# Tecleator.net
KiCad netlist of a schematic drawn in EAGLE
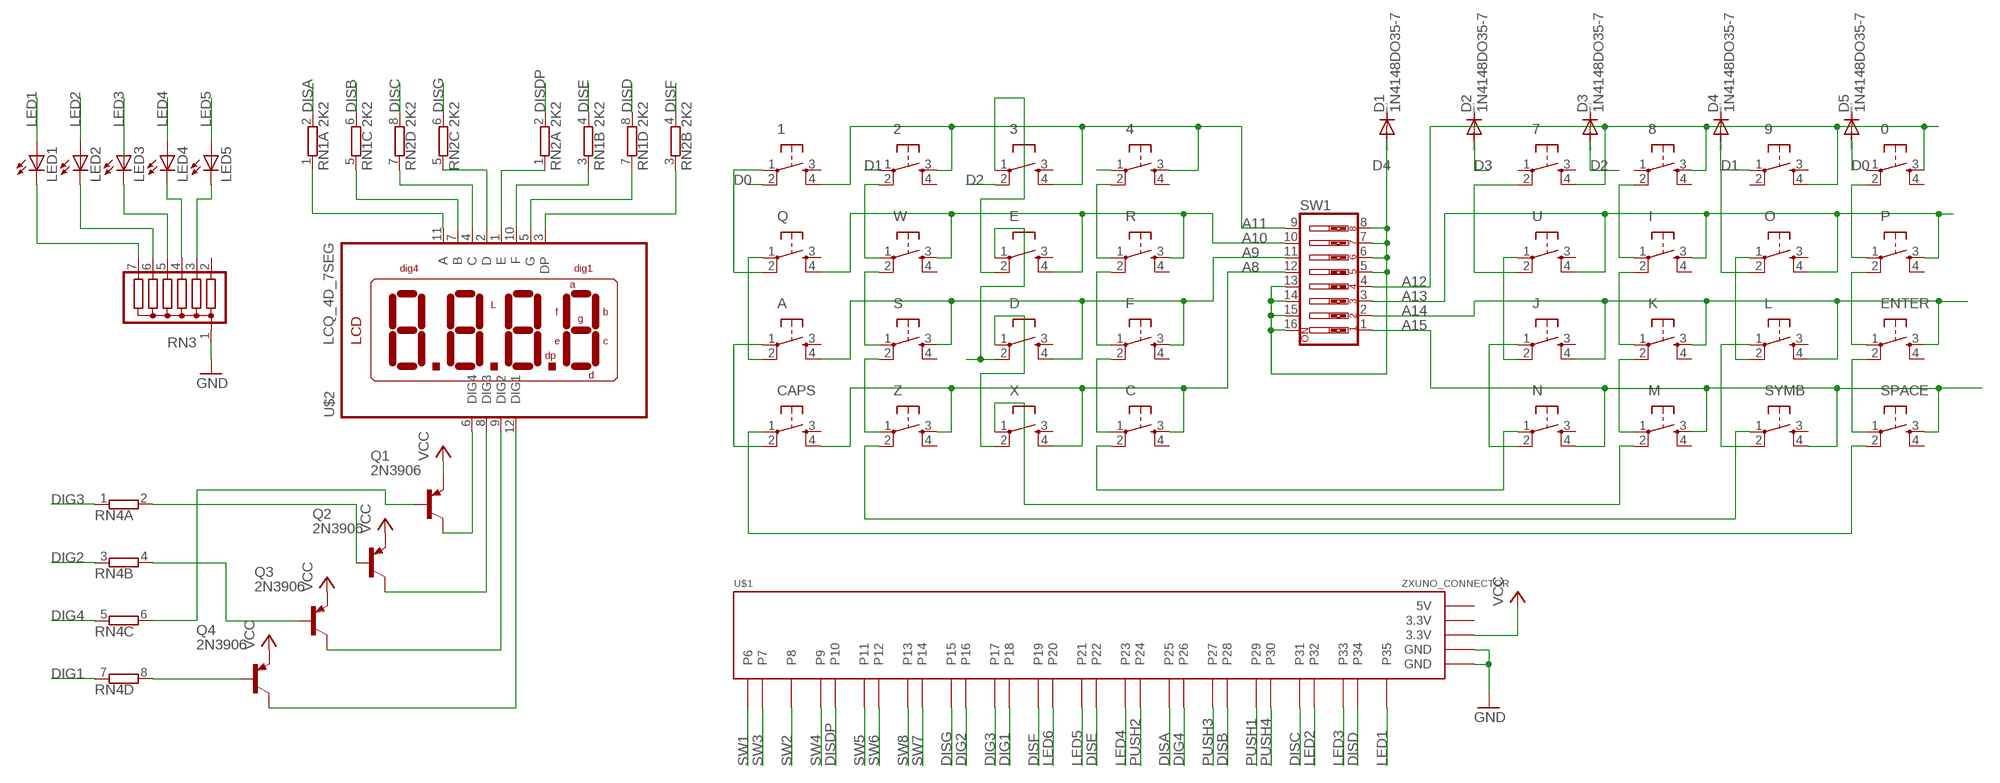
[diagram p0: schematic, sheet 1]

(export (version "E")
  (design (tool "Eeschema 10.0.6"))
  (components
    (comp (ref "0")
      (value "DTS-6")
      (footprint "eagle-import:DTS-6")
      (libsource (lib "eagle-import") (part "DTS-6"))
    )
    (comp (ref "1")
      (value "DTS-6")
      (footprint "eagle-import:DTS-6")
      (libsource (lib "eagle-import") (part "DTS-6"))
    )
    (comp (ref "2")
      (value "DTS-6")
      (footprint "eagle-import:DTS-6")
      (libsource (lib "eagle-import") (part "DTS-6"))
    )
    (comp (ref "3")
      (value "DTS-6")
      (footprint "eagle-import:DTS-6")
      (libsource (lib "eagle-import") (part "DTS-6"))
    )
    (comp (ref "4")
      (value "DTS-6")
      (footprint "eagle-import:DTS-6")
      (libsource (lib "eagle-import") (part "DTS-6"))
    )
    (comp (ref "7")
      (value "DTS-6")
      (footprint "eagle-import:DTS-6")
      (libsource (lib "eagle-import") (part "DTS-6"))
    )
    (comp (ref "8")
      (value "DTS-6")
      (footprint "eagle-import:DTS-6")
      (libsource (lib "eagle-import") (part "DTS-6"))
    )
    (comp (ref "9")
      (value "DTS-6")
      (footprint "eagle-import:DTS-6")
      (libsource (lib "eagle-import") (part "DTS-6"))
    )
    (comp (ref "A")
      (value "DTS-6")
      (footprint "eagle-import:DTS-6")
      (libsource (lib "eagle-import") (part "DTS-6"))
    )
    (comp (ref "C")
      (value "DTS-6")
      (footprint "eagle-import:DTS-6")
      (libsource (lib "eagle-import") (part "DTS-6"))
    )
    (comp (ref "CAPS")
      (value "DTS-6")
      (footprint "eagle-import:DTS-6")
      (libsource (lib "eagle-import") (part "DTS-6"))
    )
    (comp (ref "D")
      (value "DTS-6")
      (footprint "eagle-import:DTS-6")
      (libsource (lib "eagle-import") (part "DTS-6"))
    )
    (comp (ref "D1")
      (value "1N4148DO35-7")
      (footprint "eagle-import:DO35-7")
      (libsource (lib "eagle-import") (part "1N4148DO35-7"))
    )
    (comp (ref "D2")
      (value "1N4148DO35-7")
      (footprint "eagle-import:DO35-7")
      (libsource (lib "eagle-import") (part "1N4148DO35-7"))
    )
    (comp (ref "D3")
      (value "1N4148DO35-7")
      (footprint "eagle-import:DO35-7")
      (libsource (lib "eagle-import") (part "1N4148DO35-7"))
    )
    (comp (ref "D4")
      (value "1N4148DO35-7")
      (footprint "eagle-import:DO35-7")
      (libsource (lib "eagle-import") (part "1N4148DO35-7"))
    )
    (comp (ref "D5")
      (value "1N4148DO35-7")
      (footprint "eagle-import:DO35-7")
      (libsource (lib "eagle-import") (part "1N4148DO35-7"))
    )
    (comp (ref "E")
      (value "DTS-6")
      (footprint "eagle-import:DTS-6")
      (libsource (lib "eagle-import") (part "DTS-6"))
    )
    (comp (ref "ENTER")
      (value "DTS-6")
      (footprint "eagle-import:DTS-6")
      (libsource (lib "eagle-import") (part "DTS-6"))
    )
    (comp (ref "F")
      (value "DTS-6")
      (footprint "eagle-import:DTS-6")
      (libsource (lib "eagle-import") (part "DTS-6"))
    )
    (comp (ref "I")
      (value "DTS-6")
      (footprint "eagle-import:DTS-6")
      (libsource (lib "eagle-import") (part "DTS-6"))
    )
    (comp (ref "J")
      (value "DTS-6")
      (footprint "eagle-import:DTS-6")
      (libsource (lib "eagle-import") (part "DTS-6"))
    )
    (comp (ref "K")
      (value "DTS-6")
      (footprint "eagle-import:DTS-6")
      (libsource (lib "eagle-import") (part "DTS-6"))
    )
    (comp (ref "L")
      (value "DTS-6")
      (footprint "eagle-import:DTS-6")
      (libsource (lib "eagle-import") (part "DTS-6"))
    )
    (comp (ref "LED1")
      (value "LED3MM")
      (footprint "eagle-import:LED3MM")
      (libsource (lib "eagle-import") (part "LED3MM"))
    )
    (comp (ref "LED2")
      (value "LED3MM")
      (footprint "eagle-import:LED3MM")
      (libsource (lib "eagle-import") (part "LED3MM"))
    )
    (comp (ref "LED3")
      (value "LED3MM")
      (footprint "eagle-import:LED3MM")
      (libsource (lib "eagle-import") (part "LED3MM"))
    )
    (comp (ref "LED4")
      (value "LED3MM")
      (footprint "eagle-import:LED3MM")
      (libsource (lib "eagle-import") (part "LED3MM"))
    )
    (comp (ref "LED5")
      (value "LED3MM")
      (footprint "eagle-import:LED3MM")
      (libsource (lib "eagle-import") (part "LED3MM"))
    )
    (comp (ref "M")
      (value "DTS-6")
      (footprint "eagle-import:DTS-6")
      (libsource (lib "eagle-import") (part "DTS-6"))
    )
    (comp (ref "N")
      (value "DTS-6")
      (footprint "eagle-import:DTS-6")
      (libsource (lib "eagle-import") (part "DTS-6"))
    )
    (comp (ref "O")
      (value "DTS-6")
      (footprint "eagle-import:DTS-6")
      (libsource (lib "eagle-import") (part "DTS-6"))
    )
    (comp (ref "P")
      (value "DTS-6")
      (footprint "eagle-import:DTS-6")
      (libsource (lib "eagle-import") (part "DTS-6"))
    )
    (comp (ref "Q")
      (value "DTS-6")
      (footprint "eagle-import:DTS-6")
      (libsource (lib "eagle-import") (part "DTS-6"))
    )
    (comp (ref "Q1")
      (value "2N3906")
      (footprint "eagle-import:TO92")
      (libsource (lib "eagle-import") (part "2N3906"))
    )
    (comp (ref "Q2")
      (value "2N3906")
      (footprint "eagle-import:TO92")
      (libsource (lib "eagle-import") (part "2N3906"))
    )
    (comp (ref "Q3")
      (value "2N3906")
      (footprint "eagle-import:TO92")
      (libsource (lib "eagle-import") (part "2N3906"))
    )
    (comp (ref "Q4")
      (value "2N3906")
      (footprint "eagle-import:TO92")
      (libsource (lib "eagle-import") (part "2N3906"))
    )
    (comp (ref "R")
      (value "DTS-6")
      (footprint "eagle-import:DTS-6")
      (libsource (lib "eagle-import") (part "DTS-6"))
    )
    (comp (ref "RN1")
      (value "2K2")
      (footprint "eagle-import:SIL8")
      (libsource (lib "eagle-import") (part "E4R"))
    )
    (comp (ref "RN2")
      (value "2K2")
      (footprint "eagle-import:SIL8")
      (libsource (lib "eagle-import") (part "E4R"))
    )
    (comp (ref "RN3")
      (value "G06R")
      (footprint "eagle-import:SIL7")
      (libsource (lib "eagle-import") (part "G06R"))
    )
    (comp (ref "RN4")
      (value "E4R")
      (footprint "eagle-import:SIL8")
      (libsource (lib "eagle-import") (part "E4R"))
    )
    (comp (ref "S")
      (value "DTS-6")
      (footprint "eagle-import:DTS-6")
      (libsource (lib "eagle-import") (part "DTS-6"))
    )
    (comp (ref "SPACE")
      (value "DTS-6")
      (footprint "eagle-import:DTS-6")
      (libsource (lib "eagle-import") (part "DTS-6"))
    )
    (comp (ref "SW1")
      (value "SW_DIP-8")
      (footprint "eagle-import:EDG-08")
      (libsource (lib "eagle-import") (part "SW_DIP-8"))
    )
    (comp (ref "SYMB")
      (value "DTS-6")
      (footprint "eagle-import:DTS-6")
      (libsource (lib "eagle-import") (part "DTS-6"))
    )
    (comp (ref "U")
      (value "DTS-6")
      (footprint "eagle-import:DTS-6")
      (libsource (lib "eagle-import") (part "DTS-6"))
    )
    (comp (ref "U$1")
      (value "ZXUNO_CONNECTOR")
      (footprint "eagle-import:ZXUNO_CONNECTOR")
      (libsource (lib "eagle-import") (part "ZXUNO_CONNECTOR"))
    )
    (comp (ref "U$2")
      (value "LCQ_4D_7SEG")
      (footprint "eagle-import:LDQ_4D_7SEG")
      (libsource (lib "eagle-import") (part "LCQ_4D_7SEG"))
    )
    (comp (ref "W")
      (value "DTS-6")
      (footprint "eagle-import:DTS-6")
      (libsource (lib "eagle-import") (part "DTS-6"))
    )
    (comp (ref "X")
      (value "DTS-6")
      (footprint "eagle-import:DTS-6")
      (libsource (lib "eagle-import") (part "DTS-6"))
    )
    (comp (ref "Z")
      (value "DTS-6")
      (footprint "eagle-import:DTS-6")
      (libsource (lib "eagle-import") (part "DTS-6"))
    )
  )
  (nets
    (net (code "1") (name "/3.3V") (class "Default")
      (node (ref "U$1") (pin "3.3V@1") (pinfunction "3.3V_3.3V@1") (pintype "power_in"))
    )
    (net (code "2") (name "/5V") (class "Default")
      (node (ref "U$1") (pin "5V") (pinfunction "5V_5V") (pintype "power_in"))
    )
    (net (code "3") (name "/A8") (class "Default")
      (node (ref "C") (pin "3") (pinfunction "3_3") (pintype "passive"))
      (node (ref "CAPS") (pin "4") (pinfunction "4_4") (pintype "passive"))
      (node (ref "SW1") (pin "12") (pinfunction "12_12") (pintype "passive"))
      (node (ref "X") (pin "4") (pinfunction "4_4") (pintype "passive"))
      (node (ref "Z") (pin "3") (pinfunction "3_3") (pintype "passive"))
    )
    (net (code "4") (name "/A9") (class "Default")
      (node (ref "A") (pin "4") (pinfunction "4_4") (pintype "passive"))
      (node (ref "D") (pin "4") (pinfunction "4_4") (pintype "passive"))
      (node (ref "F") (pin "3") (pinfunction "3_3") (pintype "passive"))
      (node (ref "S") (pin "3") (pinfunction "3_3") (pintype "passive"))
      (node (ref "SW1") (pin "11") (pinfunction "11_11") (pintype "passive"))
    )
    (net (code "5") (name "/A10") (class "Default")
      (node (ref "E") (pin "4") (pinfunction "4_4") (pintype "passive"))
      (node (ref "Q") (pin "4") (pinfunction "4_4") (pintype "passive"))
      (node (ref "R") (pin "3") (pinfunction "3_3") (pintype "passive"))
      (node (ref "SW1") (pin "10") (pinfunction "10_10") (pintype "passive"))
      (node (ref "W") (pin "3") (pinfunction "3_3") (pintype "passive"))
    )
    (net (code "6") (name "/A11") (class "Default")
      (node (ref "1") (pin "4") (pinfunction "4_4") (pintype "passive"))
      (node (ref "2") (pin "3") (pinfunction "3_3") (pintype "passive"))
      (node (ref "3") (pin "4") (pinfunction "4_4") (pintype "passive"))
      (node (ref "4") (pin "3") (pinfunction "3_3") (pintype "passive"))
      (node (ref "SW1") (pin "9") (pinfunction "9_9") (pintype "passive"))
    )
    (net (code "7") (name "/A12") (class "Default")
      (node (ref "0") (pin "3") (pinfunction "3_3") (pintype "passive"))
      (node (ref "7") (pin "4") (pinfunction "4_4") (pintype "passive"))
      (node (ref "8") (pin "3") (pinfunction "3_3") (pintype "passive"))
      (node (ref "9") (pin "4") (pinfunction "4_4") (pintype "passive"))
      (node (ref "SW1") (pin "4") (pinfunction "4_4") (pintype "passive"))
    )
    (net (code "8") (name "/A13") (class "Default")
      (node (ref "I") (pin "3") (pinfunction "3_3") (pintype "passive"))
      (node (ref "O") (pin "4") (pinfunction "4_4") (pintype "passive"))
      (node (ref "P") (pin "3") (pinfunction "3_3") (pintype "passive"))
      (node (ref "SW1") (pin "3") (pinfunction "3_3") (pintype "passive"))
      (node (ref "U") (pin "4") (pinfunction "4_4") (pintype "passive"))
    )
    (net (code "9") (name "/A14") (class "Default")
      (node (ref "ENTER") (pin "3") (pinfunction "3_3") (pintype "passive"))
      (node (ref "J") (pin "4") (pinfunction "4_4") (pintype "passive"))
      (node (ref "K") (pin "3") (pinfunction "3_3") (pintype "passive"))
      (node (ref "L") (pin "4") (pinfunction "4_4") (pintype "passive"))
      (node (ref "SW1") (pin "2") (pinfunction "2_2") (pintype "passive"))
    )
    (net (code "10") (name "/A15") (class "Default")
      (node (ref "M") (pin "3") (pinfunction "3_3") (pintype "passive"))
      (node (ref "N") (pin "4") (pinfunction "4_4") (pintype "passive"))
      (node (ref "SPACE") (pin "3") (pinfunction "3_3") (pintype "passive"))
      (node (ref "SW1") (pin "1") (pinfunction "1_1") (pintype "passive"))
      (node (ref "SYMB") (pin "4") (pinfunction "4_4") (pintype "passive"))
    )
    (net (code "11") (name "/D0") (class "Default")
      (node (ref "1") (pin "2") (pinfunction "2_2") (pintype "passive"))
      (node (ref "D5") (pin "A") (pinfunction "A_A") (pintype "passive"))
    )
    (net (code "12") (name "/D1") (class "Default")
      (node (ref "2") (pin "1") (pinfunction "1_1") (pintype "passive"))
      (node (ref "9") (pin "1") (pinfunction "1_1") (pintype "passive"))
      (node (ref "D4") (pin "A") (pinfunction "A_A") (pintype "passive"))
      (node (ref "O") (pin "2") (pinfunction "2_2") (pintype "passive"))
    )
    (net (code "13") (name "/D2") (class "Default")
      (node (ref "3") (pin "2") (pinfunction "2_2") (pintype "passive"))
      (node (ref "D3") (pin "A") (pinfunction "A_A") (pintype "passive"))
    )
    (net (code "14") (name "/D3") (class "Default")
      (node (ref "4") (pin "1") (pinfunction "1_1") (pintype "passive"))
      (node (ref "D2") (pin "A") (pinfunction "A_A") (pintype "passive"))
    )
    (net (code "15") (name "/D4") (class "Default")
      (node (ref "D1") (pin "A") (pinfunction "A_A") (pintype "passive"))
      (node (ref "SW1") (pin "13") (pinfunction "13_13") (pintype "passive"))
      (node (ref "SW1") (pin "14") (pinfunction "14_14") (pintype "passive"))
      (node (ref "SW1") (pin "15") (pinfunction "15_15") (pintype "passive"))
      (node (ref "SW1") (pin "16") (pinfunction "16_16") (pintype "passive"))
      (node (ref "SW1") (pin "5") (pinfunction "5_5") (pintype "passive"))
      (node (ref "SW1") (pin "6") (pinfunction "6_6") (pintype "passive"))
      (node (ref "SW1") (pin "7") (pinfunction "7_7") (pintype "passive"))
      (node (ref "SW1") (pin "8") (pinfunction "8_8") (pintype "passive"))
    )
    (net (code "16") (name "/DIG1") (class "Default")
      (node (ref "RN4") (pin "7") (pinfunction "1_7") (pintype "passive"))
      (node (ref "U$1") (pin "P18") (pinfunction "P18_P18") (pintype "bidirectional"))
    )
    (net (code "17") (name "/DIG2") (class "Default")
      (node (ref "RN4") (pin "3") (pinfunction "1_3") (pintype "passive"))
      (node (ref "U$1") (pin "P16") (pinfunction "P16_P16") (pintype "bidirectional"))
    )
    (net (code "18") (name "/DIG3") (class "Default")
      (node (ref "RN4") (pin "1") (pinfunction "1_1") (pintype "passive"))
      (node (ref "U$1") (pin "P17") (pinfunction "P17_P17") (pintype "bidirectional"))
    )
    (net (code "19") (name "/DIG4") (class "Default")
      (node (ref "RN4") (pin "5") (pinfunction "1_5") (pintype "passive"))
      (node (ref "U$1") (pin "P26") (pinfunction "P26_P26") (pintype "bidirectional"))
    )
    (net (code "20") (name "/DISA") (class "Default")
      (node (ref "RN1") (pin "2") (pinfunction "2_2") (pintype "passive"))
      (node (ref "U$1") (pin "P25") (pinfunction "P25_P25") (pintype "bidirectional"))
    )
    (net (code "21") (name "/DISB") (class "Default")
      (node (ref "RN1") (pin "6") (pinfunction "2_6") (pintype "passive"))
      (node (ref "U$1") (pin "P28") (pinfunction "P28_P28") (pintype "bidirectional"))
    )
    (net (code "22") (name "/DISC") (class "Default")
      (node (ref "RN2") (pin "8") (pinfunction "2_8") (pintype "passive"))
      (node (ref "U$1") (pin "P31") (pinfunction "P31_P31") (pintype "bidirectional"))
    )
    (net (code "23") (name "/DISD") (class "Default")
      (node (ref "RN1") (pin "8") (pinfunction "2_8") (pintype "passive"))
      (node (ref "U$1") (pin "P34") (pinfunction "P34_P34") (pintype "bidirectional"))
    )
    (net (code "24") (name "/DISDP") (class "Default")
      (node (ref "RN2") (pin "2") (pinfunction "2_2") (pintype "passive"))
      (node (ref "U$1") (pin "P10") (pinfunction "P10_P10") (pintype "bidirectional"))
    )
    (net (code "25") (name "/DISE") (class "Default")
      (node (ref "RN1") (pin "4") (pinfunction "2_4") (pintype "passive"))
      (node (ref "U$1") (pin "P22") (pinfunction "P22_P22") (pintype "bidirectional"))
    )
    (net (code "26") (name "/DISF") (class "Default")
      (node (ref "RN2") (pin "4") (pinfunction "2_4") (pintype "passive"))
      (node (ref "U$1") (pin "P19") (pinfunction "P19_P19") (pintype "bidirectional"))
    )
    (net (code "27") (name "/DISG") (class "Default")
      (node (ref "RN2") (pin "6") (pinfunction "2_6") (pintype "passive"))
      (node (ref "U$1") (pin "P15") (pinfunction "P15_P15") (pintype "bidirectional"))
    )
    (net (code "28") (name "/LED1") (class "Default")
      (node (ref "LED1") (pin "A") (pinfunction "A_A") (pintype "passive"))
      (node (ref "U$1") (pin "P35") (pinfunction "P35_P35") (pintype "bidirectional"))
    )
    (net (code "29") (name "/LED2") (class "Default")
      (node (ref "LED2") (pin "A") (pinfunction "A_A") (pintype "passive"))
      (node (ref "U$1") (pin "P32") (pinfunction "P32_P32") (pintype "bidirectional"))
    )
    (net (code "30") (name "/LED3") (class "Default")
      (node (ref "LED3") (pin "A") (pinfunction "A_A") (pintype "passive"))
      (node (ref "U$1") (pin "P33") (pinfunction "P33_P33") (pintype "bidirectional"))
    )
    (net (code "31") (name "/LED4") (class "Default")
      (node (ref "LED4") (pin "A") (pinfunction "A_A") (pintype "passive"))
      (node (ref "U$1") (pin "P23") (pinfunction "P23_P23") (pintype "bidirectional"))
    )
    (net (code "32") (name "/LED5") (class "Default")
      (node (ref "LED5") (pin "A") (pinfunction "A_A") (pintype "passive"))
      (node (ref "U$1") (pin "P21") (pinfunction "P21_P21") (pintype "bidirectional"))
    )
    (net (code "33") (name "/LED6") (class "Default")
      (node (ref "U$1") (pin "P20") (pinfunction "P20_P20") (pintype "bidirectional"))
    )
    (net (code "34") (name "/PUSH1") (class "Default")
      (node (ref "U$1") (pin "P29") (pinfunction "P29_P29") (pintype "bidirectional"))
    )
    (net (code "35") (name "/PUSH2") (class "Default")
      (node (ref "U$1") (pin "P24") (pinfunction "P24_P24") (pintype "bidirectional"))
    )
    (net (code "36") (name "/PUSH3") (class "Default")
      (node (ref "U$1") (pin "P27") (pinfunction "P27_P27") (pintype "bidirectional"))
    )
    (net (code "37") (name "/PUSH4") (class "Default")
      (node (ref "U$1") (pin "P30") (pinfunction "P30_P30") (pintype "bidirectional"))
    )
    (net (code "38") (name "/SW1") (class "Default")
      (node (ref "U$1") (pin "P6") (pinfunction "P6_P6") (pintype "bidirectional"))
    )
    (net (code "39") (name "/SW2") (class "Default")
      (node (ref "U$1") (pin "P8") (pinfunction "P8_P8") (pintype "bidirectional"))
    )
    (net (code "40") (name "/SW3") (class "Default")
      (node (ref "U$1") (pin "P7") (pinfunction "P7_P7") (pintype "bidirectional"))
    )
    (net (code "41") (name "/SW4") (class "Default")
      (node (ref "U$1") (pin "P9") (pinfunction "P9_P9") (pintype "bidirectional"))
    )
    (net (code "42") (name "/SW5") (class "Default")
      (node (ref "U$1") (pin "P11") (pinfunction "P11_P11") (pintype "bidirectional"))
    )
    (net (code "43") (name "/SW6") (class "Default")
      (node (ref "U$1") (pin "P12") (pinfunction "P12_P12") (pintype "bidirectional"))
    )
    (net (code "44") (name "/SW7") (class "Default")
      (node (ref "U$1") (pin "P14") (pinfunction "P14_P14") (pintype "bidirectional"))
    )
    (net (code "45") (name "/SW8") (class "Default")
      (node (ref "U$1") (pin "P13") (pinfunction "P13_P13") (pintype "bidirectional"))
    )
    (net (code "46") (name "GND") (class "Default")
      (node (ref "RN3") (pin "1") (pinfunction "1_1") (pintype "passive"))
      (node (ref "U$1") (pin "GND@1") (pinfunction "GND_GND@1") (pintype "power_in"))
      (node (ref "U$1") (pin "GND@2") (pinfunction "GND_GND@2") (pintype "power_in"))
    )
    (net (code "47") (name "Net-(0-Pad2)") (class "Default")
      (node (ref "0") (pin "2") (pinfunction "2_2") (pintype "passive"))
      (node (ref "P") (pin "1") (pinfunction "1_1") (pintype "passive"))
    )
    (net (code "48") (name "Net-(1-Pad1)") (class "Default")
      (node (ref "1") (pin "1") (pinfunction "1_1") (pintype "passive"))
      (node (ref "Q") (pin "2") (pinfunction "2_2") (pintype "passive"))
    )
    (net (code "49") (name "Net-(2-Pad2)") (class "Default")
      (node (ref "2") (pin "2") (pinfunction "2_2") (pintype "passive"))
      (node (ref "W") (pin "1") (pinfunction "1_1") (pintype "passive"))
    )
    (net (code "50") (name "Net-(3-Pad1)") (class "Default")
      (node (ref "3") (pin "1") (pinfunction "1_1") (pintype "passive"))
      (node (ref "E") (pin "2") (pinfunction "2_2") (pintype "passive"))
    )
    (net (code "51") (name "Net-(4-Pad2)") (class "Default")
      (node (ref "4") (pin "2") (pinfunction "2_2") (pintype "passive"))
      (node (ref "R") (pin "1") (pinfunction "1_1") (pintype "passive"))
    )
    (net (code "52") (name "Net-(7-Pad2)") (class "Default")
      (node (ref "7") (pin "2") (pinfunction "2_2") (pintype "passive"))
      (node (ref "U") (pin "2") (pinfunction "2_2") (pintype "passive"))
    )
    (net (code "53") (name "Net-(8-Pad2)") (class "Default")
      (node (ref "8") (pin "2") (pinfunction "2_2") (pintype "passive"))
      (node (ref "I") (pin "1") (pinfunction "1_1") (pintype "passive"))
    )
    (net (code "54") (name "Net-(A-Pad1)") (class "Default")
      (node (ref "A") (pin "1") (pinfunction "1_1") (pintype "passive"))
      (node (ref "CAPS") (pin "2") (pinfunction "2_2") (pintype "passive"))
    )
    (net (code "55") (name "Net-(A-Pad2)") (class "Default")
      (node (ref "A") (pin "2") (pinfunction "2_2") (pintype "passive"))
      (node (ref "Q") (pin "1") (pinfunction "1_1") (pintype "passive"))
    )
    (net (code "56") (name "Net-(C-Pad1)") (class "Default")
      (node (ref "C") (pin "1") (pinfunction "1_1") (pintype "passive"))
      (node (ref "F") (pin "2") (pinfunction "2_2") (pintype "passive"))
    )
    (net (code "57") (name "Net-(C-Pad2)") (class "Default")
      (node (ref "C") (pin "2") (pinfunction "2_2") (pintype "passive"))
      (node (ref "N") (pin "1") (pinfunction "1_1") (pintype "passive"))
    )
    (net (code "58") (name "Net-(CAPS-Pad1)") (class "Default")
      (node (ref "CAPS") (pin "1") (pinfunction "1_1") (pintype "passive"))
      (node (ref "SPACE") (pin "2") (pinfunction "2_2") (pintype "passive"))
    )
    (net (code "59") (name "Net-(D-Pad1)") (class "Default")
      (node (ref "D") (pin "1") (pinfunction "1_1") (pintype "passive"))
      (node (ref "X") (pin "2") (pinfunction "2_2") (pintype "passive"))
    )
    (net (code "60") (name "Net-(D-Pad2)") (class "Default")
      (node (ref "D") (pin "2") (pinfunction "2_2") (pintype "passive"))
      (node (ref "E") (pin "1") (pinfunction "1_1") (pintype "passive"))
    )
    (net (code "61") (name "Net-(ENTER-Pad1)") (class "Default")
      (node (ref "ENTER") (pin "1") (pinfunction "1_1") (pintype "passive"))
      (node (ref "P") (pin "2") (pinfunction "2_2") (pintype "passive"))
    )
    (net (code "62") (name "Net-(ENTER-Pad2)") (class "Default")
      (node (ref "ENTER") (pin "2") (pinfunction "2_2") (pintype "passive"))
      (node (ref "SPACE") (pin "1") (pinfunction "1_1") (pintype "passive"))
    )
    (net (code "63") (name "Net-(F-Pad1)") (class "Default")
      (node (ref "F") (pin "1") (pinfunction "1_1") (pintype "passive"))
      (node (ref "R") (pin "2") (pinfunction "2_2") (pintype "passive"))
    )
    (net (code "64") (name "Net-(I-Pad2)") (class "Default")
      (node (ref "I") (pin "2") (pinfunction "2_2") (pintype "passive"))
      (node (ref "K") (pin "1") (pinfunction "1_1") (pintype "passive"))
    )
    (net (code "65") (name "Net-(J-Pad1)") (class "Default")
      (node (ref "J") (pin "1") (pinfunction "1_1") (pintype "passive"))
      (node (ref "N") (pin "2") (pinfunction "2_2") (pintype "passive"))
    )
    (net (code "66") (name "Net-(J-Pad2)") (class "Default")
      (node (ref "J") (pin "2") (pinfunction "2_2") (pintype "passive"))
      (node (ref "U") (pin "1") (pinfunction "1_1") (pintype "passive"))
    )
    (net (code "67") (name "Net-(K-Pad2)") (class "Default")
      (node (ref "K") (pin "2") (pinfunction "2_2") (pintype "passive"))
      (node (ref "M") (pin "1") (pinfunction "1_1") (pintype "passive"))
    )
    (net (code "68") (name "Net-(L-Pad1)") (class "Default")
      (node (ref "L") (pin "1") (pinfunction "1_1") (pintype "passive"))
      (node (ref "SYMB") (pin "2") (pinfunction "2_2") (pintype "passive"))
    )
    (net (code "69") (name "Net-(L-Pad2)") (class "Default")
      (node (ref "L") (pin "2") (pinfunction "2_2") (pintype "passive"))
      (node (ref "O") (pin "1") (pinfunction "1_1") (pintype "passive"))
    )
    (net (code "70") (name "Net-(LED1-C)") (class "Default")
      (node (ref "LED1") (pin "K") (pinfunction "C_K") (pintype "passive"))
      (node (ref "RN3") (pin "7") (pinfunction "7_7") (pintype "passive"))
    )
    (net (code "71") (name "Net-(LED2-C)") (class "Default")
      (node (ref "LED2") (pin "K") (pinfunction "C_K") (pintype "passive"))
      (node (ref "RN3") (pin "6") (pinfunction "6_6") (pintype "passive"))
    )
    (net (code "72") (name "Net-(LED3-C)") (class "Default")
      (node (ref "LED3") (pin "K") (pinfunction "C_K") (pintype "passive"))
      (node (ref "RN3") (pin "5") (pinfunction "5_5") (pintype "passive"))
    )
    (net (code "73") (name "Net-(LED4-C)") (class "Default")
      (node (ref "LED4") (pin "K") (pinfunction "C_K") (pintype "passive"))
      (node (ref "RN3") (pin "4") (pinfunction "4_4") (pintype "passive"))
    )
    (net (code "74") (name "Net-(LED5-C)") (class "Default")
      (node (ref "LED5") (pin "K") (pinfunction "C_K") (pintype "passive"))
      (node (ref "RN3") (pin "3") (pinfunction "3_3") (pintype "passive"))
    )
    (net (code "75") (name "Net-(M-Pad2)") (class "Default")
      (node (ref "M") (pin "2") (pinfunction "2_2") (pintype "passive"))
      (node (ref "X") (pin "1") (pinfunction "1_1") (pintype "passive"))
    )
    (net (code "76") (name "Net-(Q1-B)") (class "Default")
      (node (ref "Q1") (pin "2") (pinfunction "B_2") (pintype "passive"))
      (node (ref "RN4") (pin "6") (pinfunction "2_6") (pintype "passive"))
    )
    (net (code "77") (name "Net-(Q1-C)") (class "Default")
      (node (ref "Q1") (pin "1") (pinfunction "C_1") (pintype "passive"))
      (node (ref "U$2") (pin "6") (pinfunction "DIG4_6") (pintype "input"))
    )
    (net (code "78") (name "Net-(Q2-B)") (class "Default")
      (node (ref "Q2") (pin "2") (pinfunction "B_2") (pintype "passive"))
      (node (ref "RN4") (pin "2") (pinfunction "2_2") (pintype "passive"))
    )
    (net (code "79") (name "Net-(Q2-C)") (class "Default")
      (node (ref "Q2") (pin "1") (pinfunction "C_1") (pintype "passive"))
      (node (ref "U$2") (pin "8") (pinfunction "DIG3_8") (pintype "input"))
    )
    (net (code "80") (name "Net-(Q3-B)") (class "Default")
      (node (ref "Q3") (pin "2") (pinfunction "B_2") (pintype "passive"))
      (node (ref "RN4") (pin "4") (pinfunction "2_4") (pintype "passive"))
    )
    (net (code "81") (name "Net-(Q3-C)") (class "Default")
      (node (ref "Q3") (pin "1") (pinfunction "C_1") (pintype "passive"))
      (node (ref "U$2") (pin "9") (pinfunction "DIG2_9") (pintype "input"))
    )
    (net (code "82") (name "Net-(Q4-B)") (class "Default")
      (node (ref "Q4") (pin "2") (pinfunction "B_2") (pintype "passive"))
      (node (ref "RN4") (pin "8") (pinfunction "2_8") (pintype "passive"))
    )
    (net (code "83") (name "Net-(Q4-C)") (class "Default")
      (node (ref "Q4") (pin "1") (pinfunction "C_1") (pintype "passive"))
      (node (ref "U$2") (pin "12") (pinfunction "DIG1_12") (pintype "input"))
    )
    (net (code "84") (name "Net-(RN1B-1)") (class "Default")
      (node (ref "RN1") (pin "3") (pinfunction "1_3") (pintype "passive"))
      (node (ref "U$2") (pin "10") (pinfunction "F_10") (pintype "input"))
    )
    (net (code "85") (name "Net-(RN1C-1)") (class "Default")
      (node (ref "RN1") (pin "5") (pinfunction "1_5") (pintype "passive"))
      (node (ref "U$2") (pin "7") (pinfunction "B_7") (pintype "input"))
    )
    (net (code "86") (name "Net-(RN1D-1)") (class "Default")
      (node (ref "RN1") (pin "7") (pinfunction "1_7") (pintype "passive"))
      (node (ref "U$2") (pin "5") (pinfunction "G_5") (pintype "input"))
    )
    (net (code "87") (name "Net-(RN2B-1)") (class "Default")
      (node (ref "RN2") (pin "3") (pinfunction "1_3") (pintype "passive"))
      (node (ref "U$2") (pin "3") (pinfunction "DP_3") (pintype "input"))
    )
    (net (code "88") (name "Net-(RN2C-1)") (class "Default")
      (node (ref "RN2") (pin "5") (pinfunction "1_5") (pintype "passive"))
      (node (ref "U$2") (pin "2") (pinfunction "D_2") (pintype "input"))
    )
    (net (code "89") (name "Net-(RN2D-1)") (class "Default")
      (node (ref "RN2") (pin "7") (pinfunction "1_7") (pintype "passive"))
      (node (ref "U$2") (pin "4") (pinfunction "C_4") (pintype "input"))
    )
    (net (code "90") (name "Net-(S-Pad1)") (class "Default")
      (node (ref "S") (pin "1") (pinfunction "1_1") (pintype "passive"))
      (node (ref "W") (pin "2") (pinfunction "2_2") (pintype "passive"))
    )
    (net (code "91") (name "Net-(S-Pad2)") (class "Default")
      (node (ref "S") (pin "2") (pinfunction "2_2") (pintype "passive"))
      (node (ref "Z") (pin "1") (pinfunction "1_1") (pintype "passive"))
    )
    (net (code "92") (name "Net-(SYMB-Pad1)") (class "Default")
      (node (ref "SYMB") (pin "1") (pinfunction "1_1") (pintype "passive"))
      (node (ref "Z") (pin "2") (pinfunction "2_2") (pintype "passive"))
    )
    (net (code "93") (name "Net-(U$2-A)") (class "Default")
      (node (ref "RN1") (pin "1") (pinfunction "1_1") (pintype "passive"))
      (node (ref "U$2") (pin "11") (pinfunction "A_11") (pintype "input"))
    )
    (net (code "94") (name "Net-(U$2-E)") (class "Default")
      (node (ref "RN2") (pin "1") (pinfunction "1_1") (pintype "passive"))
      (node (ref "U$2") (pin "1") (pinfunction "E_1") (pintype "input"))
    )
    (net (code "95") (name "VCC") (class "Default")
      (node (ref "Q1") (pin "3") (pinfunction "E_3") (pintype "passive"))
      (node (ref "Q2") (pin "3") (pinfunction "E_3") (pintype "passive"))
      (node (ref "Q3") (pin "3") (pinfunction "E_3") (pintype "passive"))
      (node (ref "Q4") (pin "3") (pinfunction "E_3") (pintype "passive"))
      (node (ref "U$1") (pin "3.3V@2") (pinfunction "3.3V_3.3V@2") (pintype "power_in"))
    )
    (net (code "96") (name "unconnected-(0-Pad1)") (class "Default")
      (node (ref "0") (pin "1") (pinfunction "1_1") (pintype "passive"))
    )
    (net (code "97") (name "unconnected-(0-Pad4)") (class "Default")
      (node (ref "0") (pin "4") (pinfunction "4_4") (pintype "passive"))
    )
    (net (code "98") (name "unconnected-(1-Pad3)") (class "Default")
      (node (ref "1") (pin "3") (pinfunction "3_3") (pintype "passive"))
    )
    (net (code "99") (name "unconnected-(2-Pad4)") (class "Default")
      (node (ref "2") (pin "4") (pinfunction "4_4") (pintype "passive"))
    )
    (net (code "100") (name "unconnected-(3-Pad3)") (class "Default")
      (node (ref "3") (pin "3") (pinfunction "3_3") (pintype "passive"))
    )
    (net (code "101") (name "unconnected-(4-Pad4)") (class "Default")
      (node (ref "4") (pin "4") (pinfunction "4_4") (pintype "passive"))
    )
    (net (code "102") (name "unconnected-(7-Pad1)") (class "Default")
      (node (ref "7") (pin "1") (pinfunction "1_1") (pintype "passive"))
    )
    (net (code "103") (name "unconnected-(7-Pad3)") (class "Default")
      (node (ref "7") (pin "3") (pinfunction "3_3") (pintype "passive"))
    )
    (net (code "104") (name "unconnected-(8-Pad1)") (class "Default")
      (node (ref "8") (pin "1") (pinfunction "1_1") (pintype "passive"))
    )
    (net (code "105") (name "unconnected-(8-Pad4)") (class "Default")
      (node (ref "8") (pin "4") (pinfunction "4_4") (pintype "passive"))
    )
    (net (code "106") (name "unconnected-(9-Pad2)") (class "Default")
      (node (ref "9") (pin "2") (pinfunction "2_2") (pintype "passive"))
    )
    (net (code "107") (name "unconnected-(9-Pad3)") (class "Default")
      (node (ref "9") (pin "3") (pinfunction "3_3") (pintype "passive"))
    )
    (net (code "108") (name "unconnected-(A-Pad3)") (class "Default")
      (node (ref "A") (pin "3") (pinfunction "3_3") (pintype "passive"))
    )
    (net (code "109") (name "unconnected-(C-Pad4)") (class "Default")
      (node (ref "C") (pin "4") (pinfunction "4_4") (pintype "passive"))
    )
    (net (code "110") (name "unconnected-(CAPS-Pad3)") (class "Default")
      (node (ref "CAPS") (pin "3") (pinfunction "3_3") (pintype "passive"))
    )
    (net (code "111") (name "unconnected-(D-Pad3)") (class "Default")
      (node (ref "D") (pin "3") (pinfunction "3_3") (pintype "passive"))
    )
    (net (code "112") (name "unconnected-(D1-PadC)") (class "Default")
      (node (ref "D1") (pin "C") (pinfunction "C_C") (pintype "passive"))
    )
    (net (code "113") (name "unconnected-(D2-PadC)") (class "Default")
      (node (ref "D2") (pin "C") (pinfunction "C_C") (pintype "passive"))
    )
    (net (code "114") (name "unconnected-(D3-PadC)") (class "Default")
      (node (ref "D3") (pin "C") (pinfunction "C_C") (pintype "passive"))
    )
    (net (code "115") (name "unconnected-(D4-PadC)") (class "Default")
      (node (ref "D4") (pin "C") (pinfunction "C_C") (pintype "passive"))
    )
    (net (code "116") (name "unconnected-(D5-PadC)") (class "Default")
      (node (ref "D5") (pin "C") (pinfunction "C_C") (pintype "passive"))
    )
    (net (code "117") (name "unconnected-(E-Pad3)") (class "Default")
      (node (ref "E") (pin "3") (pinfunction "3_3") (pintype "passive"))
    )
    (net (code "118") (name "unconnected-(ENTER-Pad4)") (class "Default")
      (node (ref "ENTER") (pin "4") (pinfunction "4_4") (pintype "passive"))
    )
    (net (code "119") (name "unconnected-(F-Pad4)") (class "Default")
      (node (ref "F") (pin "4") (pinfunction "4_4") (pintype "passive"))
    )
    (net (code "120") (name "unconnected-(I-Pad4)") (class "Default")
      (node (ref "I") (pin "4") (pinfunction "4_4") (pintype "passive"))
    )
    (net (code "121") (name "unconnected-(J-Pad3)") (class "Default")
      (node (ref "J") (pin "3") (pinfunction "3_3") (pintype "passive"))
    )
    (net (code "122") (name "unconnected-(K-Pad4)") (class "Default")
      (node (ref "K") (pin "4") (pinfunction "4_4") (pintype "passive"))
    )
    (net (code "123") (name "unconnected-(L-Pad3)") (class "Default")
      (node (ref "L") (pin "3") (pinfunction "3_3") (pintype "passive"))
    )
    (net (code "124") (name "unconnected-(M-Pad4)") (class "Default")
      (node (ref "M") (pin "4") (pinfunction "4_4") (pintype "passive"))
    )
    (net (code "125") (name "unconnected-(N-Pad3)") (class "Default")
      (node (ref "N") (pin "3") (pinfunction "3_3") (pintype "passive"))
    )
    (net (code "126") (name "unconnected-(O-Pad3)") (class "Default")
      (node (ref "O") (pin "3") (pinfunction "3_3") (pintype "passive"))
    )
    (net (code "127") (name "unconnected-(P-Pad4)") (class "Default")
      (node (ref "P") (pin "4") (pinfunction "4_4") (pintype "passive"))
    )
    (net (code "128") (name "unconnected-(Q-Pad3)") (class "Default")
      (node (ref "Q") (pin "3") (pinfunction "3_3") (pintype "passive"))
    )
    (net (code "129") (name "unconnected-(R-Pad4)") (class "Default")
      (node (ref "R") (pin "4") (pinfunction "4_4") (pintype "passive"))
    )
    (net (code "130") (name "unconnected-(RN3-Pad2)") (class "Default")
      (node (ref "RN3") (pin "2") (pinfunction "2_2") (pintype "passive"))
    )
    (net (code "131") (name "unconnected-(S-Pad4)") (class "Default")
      (node (ref "S") (pin "4") (pinfunction "4_4") (pintype "passive"))
    )
    (net (code "132") (name "unconnected-(SPACE-Pad4)") (class "Default")
      (node (ref "SPACE") (pin "4") (pinfunction "4_4") (pintype "passive"))
    )
    (net (code "133") (name "unconnected-(SYMB-Pad3)") (class "Default")
      (node (ref "SYMB") (pin "3") (pinfunction "3_3") (pintype "passive"))
    )
    (net (code "134") (name "unconnected-(U-Pad3)") (class "Default")
      (node (ref "U") (pin "3") (pinfunction "3_3") (pintype "passive"))
    )
    (net (code "135") (name "unconnected-(W-Pad4)") (class "Default")
      (node (ref "W") (pin "4") (pinfunction "4_4") (pintype "passive"))
    )
    (net (code "136") (name "unconnected-(X-Pad3)") (class "Default")
      (node (ref "X") (pin "3") (pinfunction "3_3") (pintype "passive"))
    )
    (net (code "137") (name "unconnected-(Z-Pad4)") (class "Default")
      (node (ref "Z") (pin "4") (pinfunction "4_4") (pintype "passive"))
    )
  )
)
